# interfacciaAtMega2560.net
KiCad netlist of a schematic drawn in EAGLE
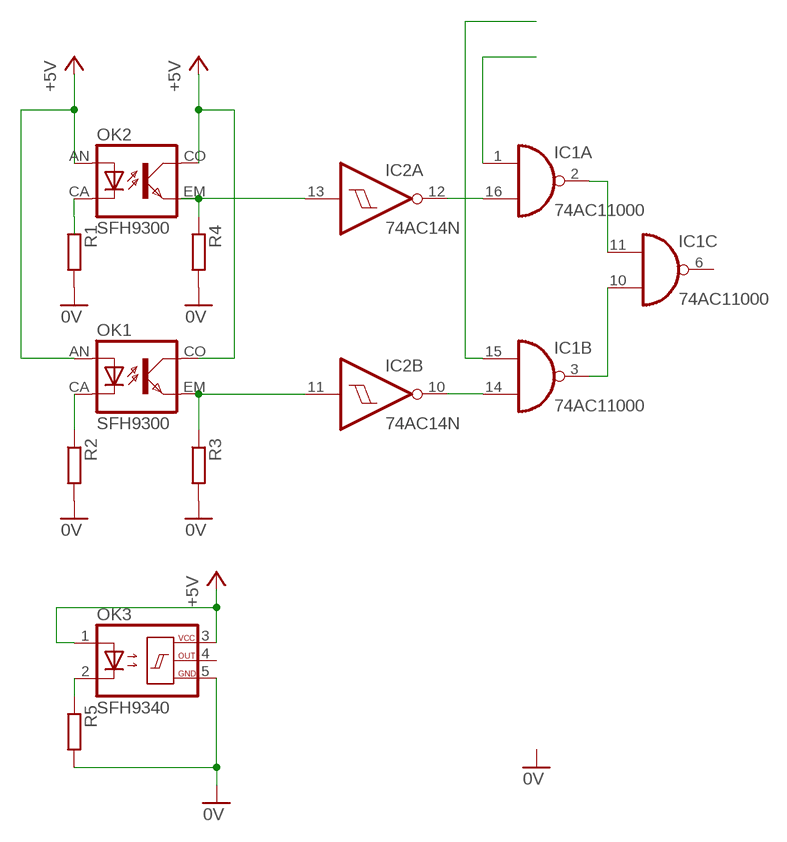
[diagram p0: schematic, sheet 1]

(export (version "E")
  (design (tool "Eeschema 10.0.6"))
  (components
    (comp (ref "IC1")
      (value "74AC11000")
      (footprint "eagle-import:DIL16")
      (libsource (lib "eagle-import") (part "74AC11000"))
    )
    (comp (ref "IC2")
      (value "74AC14N")
      (footprint "eagle-import:DIL14")
      (libsource (lib "eagle-import") (part "7414NAC"))
    )
    (comp (ref "OK1")
      (value "SFH9300")
      (footprint "eagle-import:SFH9300")
      (libsource (lib "eagle-import") (part "SFH9300"))
    )
    (comp (ref "OK2")
      (value "SFH9300")
      (footprint "eagle-import:SFH9300")
      (libsource (lib "eagle-import") (part "SFH9300"))
    )
    (comp (ref "OK3")
      (value "SFH9340")
      (footprint "eagle-import:SFH9340")
      (libsource (lib "eagle-import") (part "SFH9340"))
    )
    (comp (ref "R1")
      (value "R-EU_0411/12")
      (footprint "eagle-import:0411_12")
      (libsource (lib "eagle-import") (part "R-EU_0411/12"))
    )
    (comp (ref "R2")
      (value "R-EU_0411/12")
      (footprint "eagle-import:0411_12")
      (libsource (lib "eagle-import") (part "R-EU_0411/12"))
    )
    (comp (ref "R3")
      (value "R-EU_0411/12")
      (footprint "eagle-import:0411_12")
      (libsource (lib "eagle-import") (part "R-EU_0411/12"))
    )
    (comp (ref "R4")
      (value "R-EU_0411/12")
      (footprint "eagle-import:0411_12")
      (libsource (lib "eagle-import") (part "R-EU_0411/12"))
    )
    (comp (ref "R5")
      (value "R-EU_0411/12")
      (footprint "eagle-import:0411_12")
      (libsource (lib "eagle-import") (part "R-EU_0411/12"))
    )
  )
  (nets
    (net (code "1") (name "+5V") (class "Default")
      (node (ref "OK1") (pin "AN") (pinfunction "A_AN") (pintype "passive"))
      (node (ref "OK1") (pin "CO") (pinfunction "COL_CO") (pintype "passive"))
      (node (ref "OK2") (pin "AN") (pinfunction "A_AN") (pintype "passive"))
      (node (ref "OK2") (pin "CO") (pinfunction "COL_CO") (pintype "passive"))
      (node (ref "OK3") (pin "1") (pinfunction "A_1") (pintype "passive"))
      (node (ref "OK3") (pin "3") (pinfunction "VCC_3") (pintype "passive"))
    )
    (net (code "2") (name "0V") (class "Default")
      (node (ref "OK3") (pin "5") (pinfunction "GND_5") (pintype "passive"))
      (node (ref "R1") (pin "2") (pinfunction "2_2") (pintype "passive"))
      (node (ref "R2") (pin "2") (pinfunction "2_2") (pintype "passive"))
      (node (ref "R3") (pin "2") (pinfunction "2_2") (pintype "passive"))
      (node (ref "R4") (pin "2") (pinfunction "2_2") (pintype "passive"))
      (node (ref "R5") (pin "2") (pinfunction "2_2") (pintype "passive"))
    )
    (net (code "3") (name "Net-(IC1A-I1)") (class "Default")
      (node (ref "IC1") (pin "16") (pinfunction "I1_16") (pintype "input"))
      (node (ref "IC2") (pin "12") (pinfunction "O_12") (pintype "output"))
    )
    (net (code "4") (name "Net-(IC1A-O)") (class "Default")
      (node (ref "IC1") (pin "11") (pinfunction "I0_11") (pintype "input"))
      (node (ref "IC1") (pin "2") (pinfunction "O_2") (pintype "output"))
    )
    (net (code "5") (name "Net-(IC1B-I1)") (class "Default")
      (node (ref "IC1") (pin "14") (pinfunction "I1_14") (pintype "input"))
      (node (ref "IC2") (pin "10") (pinfunction "O_10") (pintype "output"))
    )
    (net (code "6") (name "Net-(IC1B-O)") (class "Default")
      (node (ref "IC1") (pin "10") (pinfunction "I1_10") (pintype "input"))
      (node (ref "IC1") (pin "3") (pinfunction "O_3") (pintype "output"))
    )
    (net (code "7") (name "Net-(IC2A-I)") (class "Default")
      (node (ref "IC2") (pin "13") (pinfunction "I_13") (pintype "input"))
      (node (ref "OK2") (pin "EM") (pinfunction "EMIT_EM") (pintype "passive"))
      (node (ref "R4") (pin "1") (pinfunction "1_1") (pintype "passive"))
    )
    (net (code "8") (name "Net-(IC2B-I)") (class "Default")
      (node (ref "IC2") (pin "11") (pinfunction "I_11") (pintype "input"))
      (node (ref "OK1") (pin "EM") (pinfunction "EMIT_EM") (pintype "passive"))
      (node (ref "R3") (pin "1") (pinfunction "1_1") (pintype "passive"))
    )
    (net (code "9") (name "Net-(OK1-C)") (class "Default")
      (node (ref "OK1") (pin "CA") (pinfunction "C_CA") (pintype "passive"))
      (node (ref "R2") (pin "1") (pinfunction "1_1") (pintype "passive"))
    )
    (net (code "10") (name "Net-(OK2-C)") (class "Default")
      (node (ref "OK2") (pin "CA") (pinfunction "C_CA") (pintype "passive"))
      (node (ref "R1") (pin "1") (pinfunction "1_1") (pintype "passive"))
    )
    (net (code "11") (name "Net-(OK3-C)") (class "Default")
      (node (ref "OK3") (pin "2") (pinfunction "C_2") (pintype "passive"))
      (node (ref "R5") (pin "1") (pinfunction "1_1") (pintype "passive"))
    )
    (net (code "12") (name "unconnected-(IC1A-I0-Pad1)") (class "Default")
      (node (ref "IC1") (pin "1") (pinfunction "I0_1") (pintype "input"))
    )
    (net (code "13") (name "unconnected-(IC1B-I0-Pad15)") (class "Default")
      (node (ref "IC1") (pin "15") (pinfunction "I0_15") (pintype "input"))
    )
    (net (code "14") (name "unconnected-(IC1C-O-Pad6)") (class "Default")
      (node (ref "IC1") (pin "6") (pinfunction "O_6") (pintype "output"))
    )
    (net (code "15") (name "unconnected-(OK3-OUT-Pad4)") (class "Default")
      (node (ref "OK3") (pin "4") (pinfunction "OUT_4") (pintype "passive"))
    )
  )
)
